# DAQ.net
KiCad netlist of a schematic drawn in EAGLE
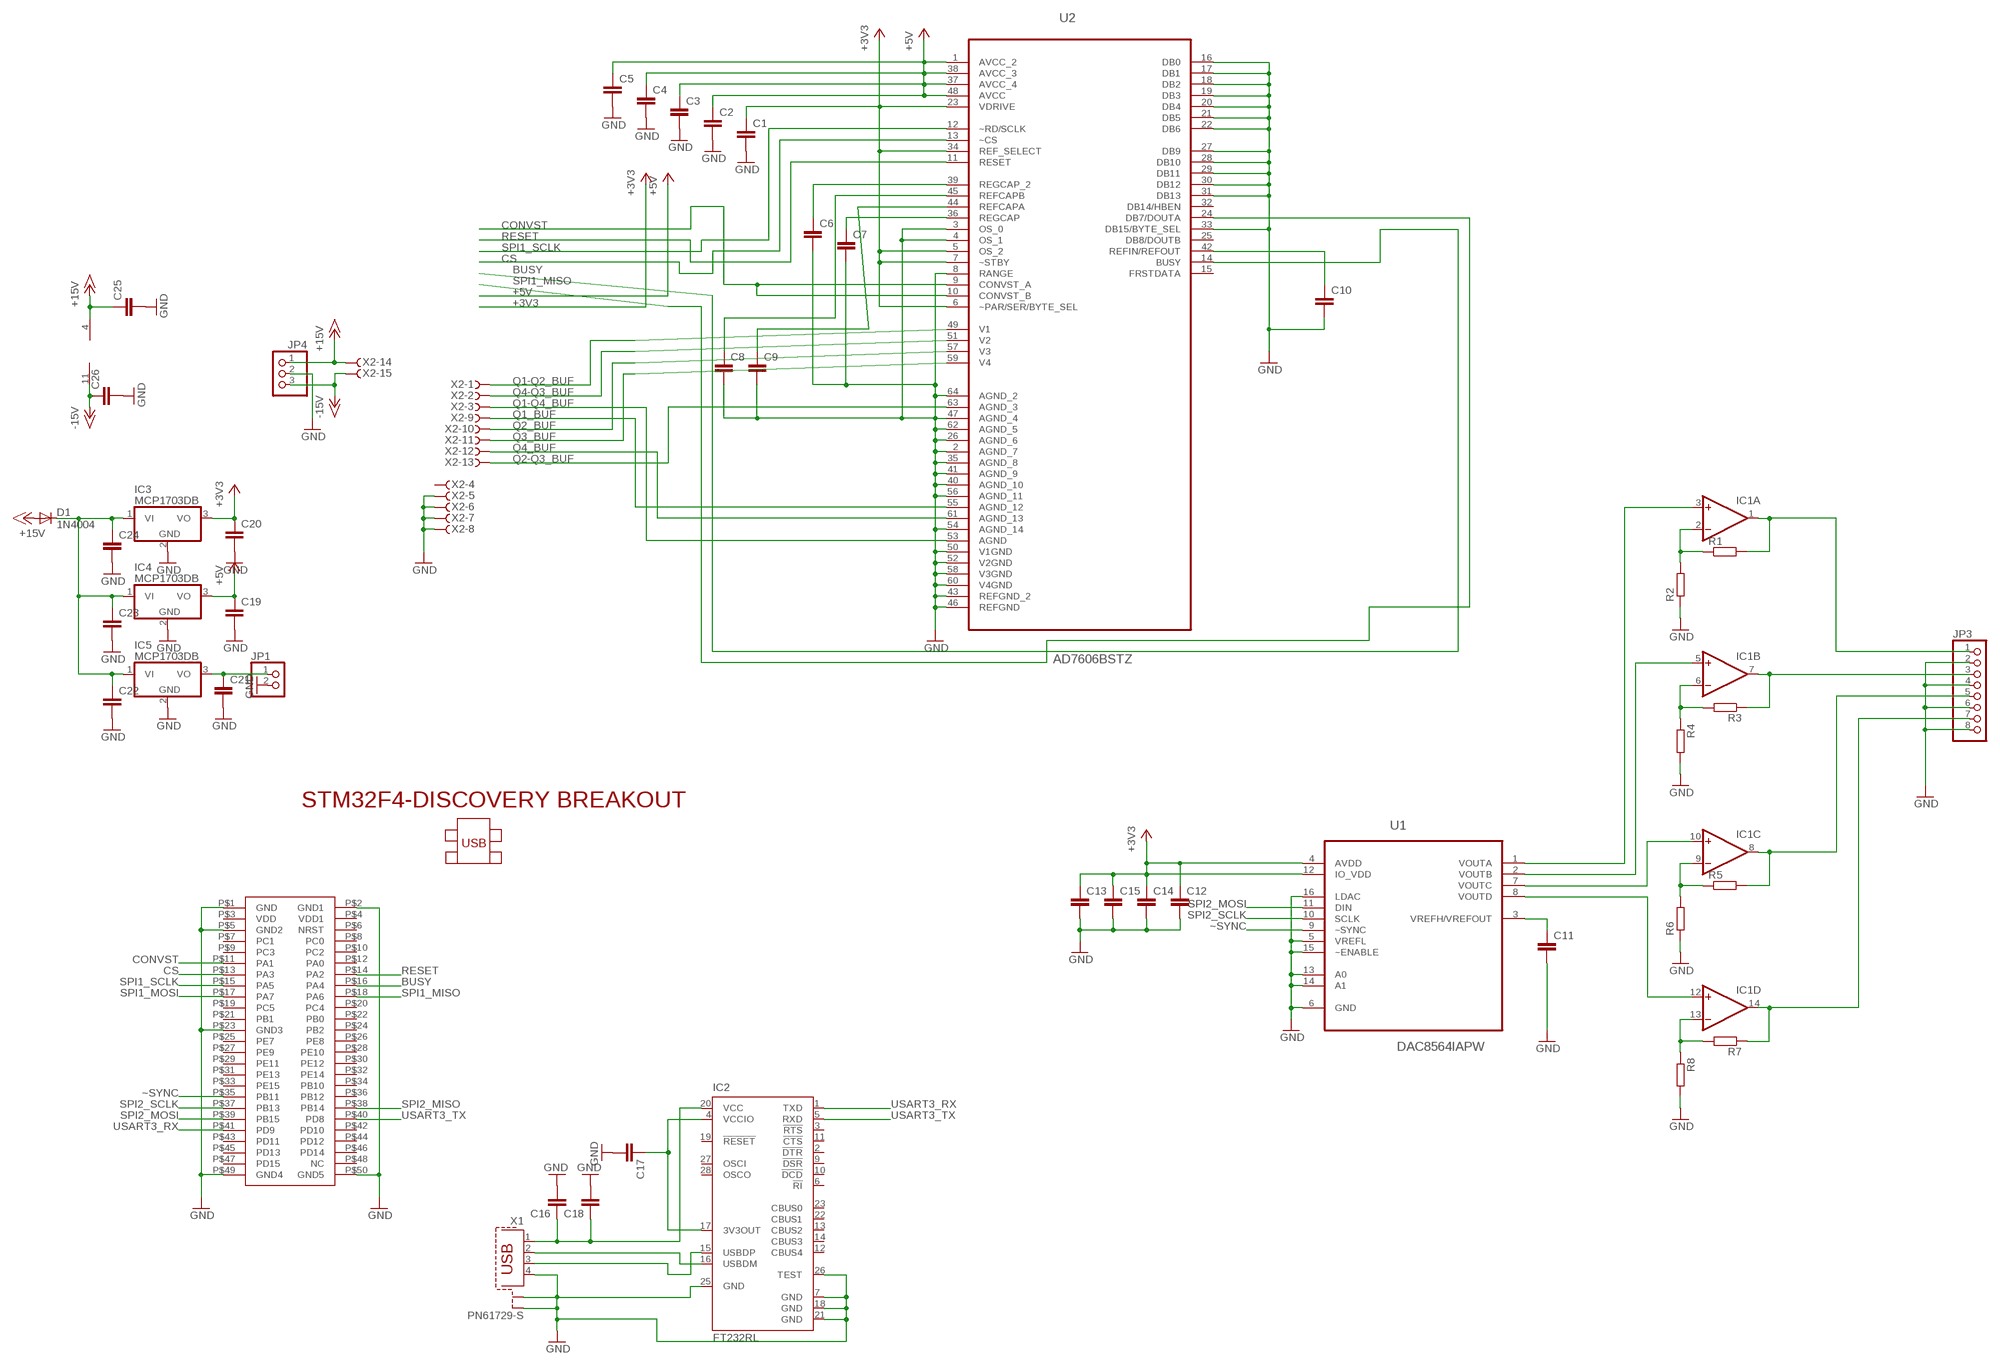
[diagram p0: schematic, sheet 1]

(export (version "E")
  (design (tool "Eeschema 10.0.6"))
  (components
    (comp (ref "C1")
      (value "C-EUC0805")
      (footprint "eagle-import:C0805")
      (libsource (lib "eagle-import") (part "C-EUC0805"))
    )
    (comp (ref "C2")
      (value "C-EUC0805")
      (footprint "eagle-import:C0805")
      (libsource (lib "eagle-import") (part "C-EUC0805"))
    )
    (comp (ref "C3")
      (value "C-EUC0805")
      (footprint "eagle-import:C0805")
      (libsource (lib "eagle-import") (part "C-EUC0805"))
    )
    (comp (ref "C4")
      (value "C-EUC0805")
      (footprint "eagle-import:C0805")
      (libsource (lib "eagle-import") (part "C-EUC0805"))
    )
    (comp (ref "C5")
      (value "C-EUC0805")
      (footprint "eagle-import:C0805")
      (libsource (lib "eagle-import") (part "C-EUC0805"))
    )
    (comp (ref "C6")
      (value "C-EUC0805")
      (footprint "eagle-import:C0805")
      (libsource (lib "eagle-import") (part "C-EUC0805"))
    )
    (comp (ref "C7")
      (value "C-EUC0805")
      (footprint "eagle-import:C0805")
      (libsource (lib "eagle-import") (part "C-EUC0805"))
    )
    (comp (ref "C8")
      (value "C-EUC0805K")
      (footprint "eagle-import:C0805K")
      (libsource (lib "eagle-import") (part "C-EUC0805K"))
    )
    (comp (ref "C9")
      (value "C-EUC0805K")
      (footprint "eagle-import:C0805K")
      (libsource (lib "eagle-import") (part "C-EUC0805K"))
    )
    (comp (ref "C10")
      (value "C-EUC0805K")
      (footprint "eagle-import:C0805K")
      (libsource (lib "eagle-import") (part "C-EUC0805K"))
    )
    (comp (ref "C11")
      (value "C-EUC0805")
      (footprint "eagle-import:C0805")
      (libsource (lib "eagle-import") (part "C-EUC0805"))
    )
    (comp (ref "C12")
      (value "C-EUC0805")
      (footprint "eagle-import:C0805")
      (libsource (lib "eagle-import") (part "C-EUC0805"))
    )
    (comp (ref "C13")
      (value "C-EUC0805")
      (footprint "eagle-import:C0805")
      (libsource (lib "eagle-import") (part "C-EUC0805"))
    )
    (comp (ref "C14")
      (value "C-EUC0805")
      (footprint "eagle-import:C0805")
      (libsource (lib "eagle-import") (part "C-EUC0805"))
    )
    (comp (ref "C15")
      (value "C-EUC0805")
      (footprint "eagle-import:C0805")
      (libsource (lib "eagle-import") (part "C-EUC0805"))
    )
    (comp (ref "C16")
      (value "C-EUC0805")
      (footprint "eagle-import:C0805")
      (libsource (lib "eagle-import") (part "C-EUC0805"))
    )
    (comp (ref "C17")
      (value "C-EUC0805")
      (footprint "eagle-import:C0805")
      (libsource (lib "eagle-import") (part "C-EUC0805"))
    )
    (comp (ref "C18")
      (value "C-EUC0805")
      (footprint "eagle-import:C0805")
      (libsource (lib "eagle-import") (part "C-EUC0805"))
    )
    (comp (ref "C19")
      (value "C-EUC0805K")
      (footprint "eagle-import:C0805K")
      (libsource (lib "eagle-import") (part "C-EUC0805K"))
    )
    (comp (ref "C20")
      (value "C-EUC0805K")
      (footprint "eagle-import:C0805K")
      (libsource (lib "eagle-import") (part "C-EUC0805K"))
    )
    (comp (ref "C21")
      (value "C-EUC0805K")
      (footprint "eagle-import:C0805K")
      (libsource (lib "eagle-import") (part "C-EUC0805K"))
    )
    (comp (ref "C22")
      (value "C-EUC0805K")
      (footprint "eagle-import:C0805K")
      (libsource (lib "eagle-import") (part "C-EUC0805K"))
    )
    (comp (ref "C23")
      (value "C-EUC0805K")
      (footprint "eagle-import:C0805K")
      (libsource (lib "eagle-import") (part "C-EUC0805K"))
    )
    (comp (ref "C24")
      (value "C-EUC0805K")
      (footprint "eagle-import:C0805K")
      (libsource (lib "eagle-import") (part "C-EUC0805K"))
    )
    (comp (ref "C25")
      (value "C-EUC0805K")
      (footprint "eagle-import:C0805K")
      (libsource (lib "eagle-import") (part "C-EUC0805K"))
    )
    (comp (ref "C26")
      (value "C-EUC0805K")
      (footprint "eagle-import:C0805K")
      (libsource (lib "eagle-import") (part "C-EUC0805K"))
    )
    (comp (ref "D1")
      (value "1N4004")
      (footprint "eagle-import:DO41-10")
      (libsource (lib "eagle-import") (part "1N4004"))
    )
    (comp (ref "IC1")
      (value "4AMP_P4+11D")
      (footprint "eagle-import:SO14")
      (libsource (lib "eagle-import") (part "4AMP_P4+11D"))
    )
    (comp (ref "IC2")
      (value "FT232RL")
      (footprint "eagle-import:SSOP28")
      (libsource (lib "eagle-import") (part "FT232RL"))
    )
    (comp (ref "IC3")
      (value "MCP1703DB")
      (footprint "eagle-import:SOT223")
      (libsource (lib "eagle-import") (part "MCP1703DB"))
    )
    (comp (ref "IC4")
      (value "MCP1703DB")
      (footprint "eagle-import:SOT223")
      (libsource (lib "eagle-import") (part "MCP1703DB"))
    )
    (comp (ref "IC5")
      (value "MCP1703DB")
      (footprint "eagle-import:SOT223")
      (libsource (lib "eagle-import") (part "MCP1703DB"))
    )
    (comp (ref "JP1")
      (value "PINHD-1X2")
      (footprint "eagle-import:1X02")
      (libsource (lib "eagle-import") (part "PINHD-1X2"))
    )
    (comp (ref "JP3")
      (value "PINHD-1X8")
      (footprint "eagle-import:1X08")
      (libsource (lib "eagle-import") (part "PINHD-1X8"))
    )
    (comp (ref "JP4")
      (value "PINHD-1X3")
      (footprint "eagle-import:1X03")
      (libsource (lib "eagle-import") (part "PINHD-1X3"))
    )
    (comp (ref "R1")
      (value "R-EU_M0805")
      (footprint "eagle-import:M0805")
      (libsource (lib "eagle-import") (part "R-EU_M0805"))
    )
    (comp (ref "R2")
      (value "R-EU_M0805")
      (footprint "eagle-import:M0805")
      (libsource (lib "eagle-import") (part "R-EU_M0805"))
    )
    (comp (ref "R3")
      (value "R-EU_M0805")
      (footprint "eagle-import:M0805")
      (libsource (lib "eagle-import") (part "R-EU_M0805"))
    )
    (comp (ref "R4")
      (value "R-EU_M0805")
      (footprint "eagle-import:M0805")
      (libsource (lib "eagle-import") (part "R-EU_M0805"))
    )
    (comp (ref "R5")
      (value "R-EU_M0805")
      (footprint "eagle-import:M0805")
      (libsource (lib "eagle-import") (part "R-EU_M0805"))
    )
    (comp (ref "R6")
      (value "R-EU_M0805")
      (footprint "eagle-import:M0805")
      (libsource (lib "eagle-import") (part "R-EU_M0805"))
    )
    (comp (ref "R7")
      (value "R-EU_M0805")
      (footprint "eagle-import:M0805")
      (libsource (lib "eagle-import") (part "R-EU_M0805"))
    )
    (comp (ref "R8")
      (value "R-EU_M0805")
      (footprint "eagle-import:M0805")
      (libsource (lib "eagle-import") (part "R-EU_M0805"))
    )
    (comp (ref "U$1")
      (value "STM32F4-DISCOVERY")
      (footprint "eagle-import:STM32F4-DISCOVERY")
      (libsource (lib "eagle-import") (part "STM32F4-DISCOVERY"))
    )
    (comp (ref "U1")
      (value "DAC8564IAPW")
      (footprint "eagle-import:SOP65P640X120-16N")
      (libsource (lib "eagle-import") (part "DAC8564IAPW"))
    )
    (comp (ref "U2")
      (value "AD7606BSTZ")
      (footprint "eagle-import:QFP50P1200X1200X160-64N")
      (libsource (lib "eagle-import") (part "AD7606BSTZ"))
    )
    (comp (ref "X1")
      (value "PN61729-S")
      (footprint "eagle-import:PN61729-S")
      (libsource (lib "eagle-import") (part "PN61729-S"))
    )
    (comp (ref "X2")
      (value "F15HDHS")
      (footprint "eagle-import:HDF15H")
      (libsource (lib "eagle-import") (part "F15?SHDH"))
    )
  )
  (nets
    (net (code "1") (name "+3V3") (class "Default")
      (node (ref "C1") (pin "1") (pinfunction "1_1") (pintype "passive"))
      (node (ref "C12") (pin "1") (pinfunction "1_1") (pintype "passive"))
      (node (ref "C13") (pin "1") (pinfunction "1_1") (pintype "passive"))
      (node (ref "C14") (pin "1") (pinfunction "1_1") (pintype "passive"))
      (node (ref "C15") (pin "1") (pinfunction "1_1") (pintype "passive"))
      (node (ref "C20") (pin "1") (pinfunction "1_1") (pintype "passive"))
      (node (ref "IC3") (pin "3") (pinfunction "VO_3") (pintype "passive"))
      (node (ref "U1") (pin "12") (pinfunction "IO_VDD_12") (pintype "power_in"))
      (node (ref "U1") (pin "4") (pinfunction "AVDD_4") (pintype "power_in"))
      (node (ref "U2") (pin "23") (pinfunction "VDRIVE_23") (pintype "power_in"))
      (node (ref "U2") (pin "34") (pinfunction "REF_SELECT_34") (pintype "input"))
      (node (ref "U2") (pin "5") (pinfunction "OS_2_5") (pintype "input"))
      (node (ref "U2") (pin "6") (pinfunction "~{PAR/SER/BYTE_SEL}_6") (pintype "input"))
      (node (ref "U2") (pin "7") (pinfunction "~{STBY}_7") (pintype "input"))
    )
    (net (code "2") (name "+5V") (class "Default")
      (node (ref "C19") (pin "1") (pinfunction "1_1") (pintype "passive"))
      (node (ref "C2") (pin "1") (pinfunction "1_1") (pintype "passive"))
      (node (ref "C3") (pin "1") (pinfunction "1_1") (pintype "passive"))
      (node (ref "C4") (pin "1") (pinfunction "1_1") (pintype "passive"))
      (node (ref "C5") (pin "1") (pinfunction "1_1") (pintype "passive"))
      (node (ref "IC4") (pin "3") (pinfunction "VO_3") (pintype "passive"))
      (node (ref "U2") (pin "1") (pinfunction "AVCC_2_1") (pintype "power_in"))
      (node (ref "U2") (pin "37") (pinfunction "AVCC_4_37") (pintype "power_in"))
      (node (ref "U2") (pin "38") (pinfunction "AVCC_3_38") (pintype "power_in"))
      (node (ref "U2") (pin "48") (pinfunction "AVCC_48") (pintype "power_in"))
    )
    (net (code "3") (name "+15V") (class "Default")
      (node (ref "C25") (pin "1") (pinfunction "1_1") (pintype "passive"))
      (node (ref "D1") (pin "A") (pinfunction "A_A") (pintype "passive"))
      (node (ref "IC1") (pin "4") (pinfunction "V+_4") (pintype "power_in"))
      (node (ref "JP4") (pin "1") (pinfunction "1_1") (pintype "passive"))
      (node (ref "X2") (pin "14") (pinfunction "F_14") (pintype "passive"))
    )
    (net (code "4") (name "-15V") (class "Default")
      (node (ref "C26") (pin "1") (pinfunction "1_1") (pintype "passive"))
      (node (ref "IC1") (pin "11") (pinfunction "V-_11") (pintype "power_in"))
      (node (ref "JP4") (pin "3") (pinfunction "3_3") (pintype "passive"))
      (node (ref "X2") (pin "15") (pinfunction "F_15") (pintype "passive"))
    )
    (net (code "5") (name "/BUSY") (class "Default")
      (node (ref "U$1") (pin "P$16") (pinfunction "PA4_P$16") (pintype "bidirectional"))
      (node (ref "U2") (pin "14") (pinfunction "BUSY_14") (pintype "output"))
    )
    (net (code "6") (name "/CONVST") (class "Default")
      (node (ref "U$1") (pin "P$11") (pinfunction "PA1_P$11") (pintype "bidirectional"))
      (node (ref "U2") (pin "10") (pinfunction "CONVST_B_10") (pintype "input"))
      (node (ref "U2") (pin "9") (pinfunction "CONVST_A_9") (pintype "input"))
    )
    (net (code "7") (name "/CS") (class "Default")
      (node (ref "U$1") (pin "P$13") (pinfunction "PA3_P$13") (pintype "bidirectional"))
      (node (ref "U2") (pin "13") (pinfunction "~{CS}_13") (pintype "input"))
    )
    (net (code "8") (name "/Q1-Q2_BUF") (class "Default")
      (node (ref "U2") (pin "49") (pinfunction "V1_49") (pintype "input"))
      (node (ref "X2") (pin "1") (pinfunction "F_1") (pintype "passive"))
    )
    (net (code "9") (name "/Q1-Q4_BUF") (class "Default")
      (node (ref "U2") (pin "53") (pinfunction "AGND_53") (pintype "passive"))
      (node (ref "X2") (pin "3") (pinfunction "F_3") (pintype "passive"))
    )
    (net (code "10") (name "/Q1_BUF") (class "Default")
      (node (ref "U2") (pin "55") (pinfunction "AGND_12_55") (pintype "passive"))
      (node (ref "X2") (pin "9") (pinfunction "F_9") (pintype "passive"))
    )
    (net (code "11") (name "/Q2-Q3_BUF") (class "Default")
      (node (ref "U2") (pin "63") (pinfunction "AGND_3_63") (pintype "passive"))
      (node (ref "X2") (pin "13") (pinfunction "F_13") (pintype "passive"))
    )
    (net (code "12") (name "/Q2_BUF") (class "Default")
      (node (ref "U2") (pin "57") (pinfunction "V3_57") (pintype "input"))
      (node (ref "X2") (pin "10") (pinfunction "F_10") (pintype "passive"))
    )
    (net (code "13") (name "/Q3_BUF") (class "Default")
      (node (ref "U2") (pin "59") (pinfunction "V4_59") (pintype "input"))
      (node (ref "X2") (pin "11") (pinfunction "F_11") (pintype "passive"))
    )
    (net (code "14") (name "/Q4-Q3_BUF") (class "Default")
      (node (ref "U2") (pin "51") (pinfunction "V2_51") (pintype "input"))
      (node (ref "X2") (pin "2") (pinfunction "F_2") (pintype "passive"))
    )
    (net (code "15") (name "/Q4_BUF") (class "Default")
      (node (ref "U2") (pin "61") (pinfunction "AGND_13_61") (pintype "passive"))
      (node (ref "X2") (pin "12") (pinfunction "F_12") (pintype "passive"))
    )
    (net (code "16") (name "/RESET") (class "Default")
      (node (ref "U$1") (pin "P$14") (pinfunction "PA2_P$14") (pintype "bidirectional"))
      (node (ref "U2") (pin "11") (pinfunction "RESET_11") (pintype "input"))
    )
    (net (code "17") (name "/SPI1_MISO") (class "Default")
      (node (ref "U$1") (pin "P$18") (pinfunction "PA6_P$18") (pintype "bidirectional"))
      (node (ref "U2") (pin "24") (pinfunction "DB7/DOUTA_24") (pintype "output"))
    )
    (net (code "18") (name "/SPI1_MOSI") (class "Default")
      (node (ref "U$1") (pin "P$17") (pinfunction "PA7_P$17") (pintype "bidirectional"))
    )
    (net (code "19") (name "/SPI1_SCLK") (class "Default")
      (node (ref "U$1") (pin "P$15") (pinfunction "PA5_P$15") (pintype "bidirectional"))
      (node (ref "U2") (pin "12") (pinfunction "~{RD/SCLK}_12") (pintype "input"))
    )
    (net (code "20") (name "/SPI2_MISO") (class "Default")
      (node (ref "U$1") (pin "P$38") (pinfunction "PB14_P$38") (pintype "bidirectional"))
    )
    (net (code "21") (name "/SPI2_MOSI") (class "Default")
      (node (ref "U$1") (pin "P$39") (pinfunction "PB15_P$39") (pintype "bidirectional"))
      (node (ref "U1") (pin "11") (pinfunction "DIN_11") (pintype "input"))
    )
    (net (code "22") (name "/SPI2_SCLK") (class "Default")
      (node (ref "U$1") (pin "P$37") (pinfunction "PB13_P$37") (pintype "bidirectional"))
      (node (ref "U1") (pin "10") (pinfunction "SCLK_10") (pintype "input"))
    )
    (net (code "23") (name "/USART3_RX") (class "Default")
      (node (ref "IC2") (pin "1") (pinfunction "TXD_1") (pintype "output"))
      (node (ref "U$1") (pin "P$41") (pinfunction "PD9_P$41") (pintype "bidirectional"))
    )
    (net (code "24") (name "/USART3_TX") (class "Default")
      (node (ref "IC2") (pin "5") (pinfunction "RXD_5") (pintype "input"))
      (node (ref "U$1") (pin "P$40") (pinfunction "PD8_P$40") (pintype "bidirectional"))
    )
    (net (code "25") (name "/~{SYNC}") (class "Default")
      (node (ref "U$1") (pin "P$35") (pinfunction "PB11_P$35") (pintype "bidirectional"))
      (node (ref "U1") (pin "9") (pinfunction "~{SYNC}_9") (pintype "input"))
    )
    (net (code "26") (name "GND") (class "Default")
      (node (ref "C1") (pin "2") (pinfunction "2_2") (pintype "passive"))
      (node (ref "C10") (pin "2") (pinfunction "2_2") (pintype "passive"))
      (node (ref "C11") (pin "2") (pinfunction "2_2") (pintype "passive"))
      (node (ref "C12") (pin "2") (pinfunction "2_2") (pintype "passive"))
      (node (ref "C13") (pin "2") (pinfunction "2_2") (pintype "passive"))
      (node (ref "C14") (pin "2") (pinfunction "2_2") (pintype "passive"))
      (node (ref "C15") (pin "2") (pinfunction "2_2") (pintype "passive"))
      (node (ref "C16") (pin "2") (pinfunction "2_2") (pintype "passive"))
      (node (ref "C17") (pin "2") (pinfunction "2_2") (pintype "passive"))
      (node (ref "C18") (pin "2") (pinfunction "2_2") (pintype "passive"))
      (node (ref "C19") (pin "2") (pinfunction "2_2") (pintype "passive"))
      (node (ref "C2") (pin "2") (pinfunction "2_2") (pintype "passive"))
      (node (ref "C20") (pin "2") (pinfunction "2_2") (pintype "passive"))
      (node (ref "C21") (pin "2") (pinfunction "2_2") (pintype "passive"))
      (node (ref "C22") (pin "2") (pinfunction "2_2") (pintype "passive"))
      (node (ref "C23") (pin "2") (pinfunction "2_2") (pintype "passive"))
      (node (ref "C24") (pin "2") (pinfunction "2_2") (pintype "passive"))
      (node (ref "C25") (pin "2") (pinfunction "2_2") (pintype "passive"))
      (node (ref "C26") (pin "2") (pinfunction "2_2") (pintype "passive"))
      (node (ref "C3") (pin "2") (pinfunction "2_2") (pintype "passive"))
      (node (ref "C4") (pin "2") (pinfunction "2_2") (pintype "passive"))
      (node (ref "C5") (pin "2") (pinfunction "2_2") (pintype "passive"))
      (node (ref "C6") (pin "2") (pinfunction "2_2") (pintype "passive"))
      (node (ref "C7") (pin "2") (pinfunction "2_2") (pintype "passive"))
      (node (ref "C8") (pin "2") (pinfunction "2_2") (pintype "passive"))
      (node (ref "C9") (pin "2") (pinfunction "2_2") (pintype "passive"))
      (node (ref "IC2") (pin "18") (pinfunction "GND_18") (pintype "power_in"))
      (node (ref "IC2") (pin "21") (pinfunction "GND_21") (pintype "power_in"))
      (node (ref "IC2") (pin "25") (pinfunction "GND_25") (pintype "power_in"))
      (node (ref "IC2") (pin "26") (pinfunction "TEST_26") (pintype "input"))
      (node (ref "IC2") (pin "7") (pinfunction "GND_7") (pintype "power_in"))
      (node (ref "IC3") (pin "2") (pinfunction "GND_2") (pintype "passive"))
      (node (ref "IC4") (pin "2") (pinfunction "GND_2") (pintype "passive"))
      (node (ref "IC5") (pin "2") (pinfunction "GND_2") (pintype "passive"))
      (node (ref "JP1") (pin "2") (pinfunction "2_2") (pintype "passive"))
      (node (ref "JP3") (pin "2") (pinfunction "2_2") (pintype "passive"))
      (node (ref "JP3") (pin "4") (pinfunction "4_4") (pintype "passive"))
      (node (ref "JP3") (pin "6") (pinfunction "6_6") (pintype "passive"))
      (node (ref "JP3") (pin "8") (pinfunction "8_8") (pintype "passive"))
      (node (ref "JP4") (pin "2") (pinfunction "2_2") (pintype "passive"))
      (node (ref "R2") (pin "1") (pinfunction "1_1") (pintype "passive"))
      (node (ref "R4") (pin "2") (pinfunction "2_2") (pintype "passive"))
      (node (ref "R6") (pin "1") (pinfunction "1_1") (pintype "passive"))
      (node (ref "R8") (pin "2") (pinfunction "2_2") (pintype "passive"))
      (node (ref "U$1") (pin "P$1") (pinfunction "GND_P$1") (pintype "bidirectional"))
      (node (ref "U$1") (pin "P$2") (pinfunction "GND1_P$2") (pintype "bidirectional"))
      (node (ref "U$1") (pin "P$23") (pinfunction "GND3_P$23") (pintype "bidirectional"))
      (node (ref "U$1") (pin "P$49") (pinfunction "GND4_P$49") (pintype "bidirectional"))
      (node (ref "U$1") (pin "P$5") (pinfunction "GND2_P$5") (pintype "bidirectional"))
      (node (ref "U$1") (pin "P$50") (pinfunction "GND5_P$50") (pintype "bidirectional"))
      (node (ref "U1") (pin "13") (pinfunction "A0_13") (pintype "input"))
      (node (ref "U1") (pin "14") (pinfunction "A1_14") (pintype "input"))
      (node (ref "U1") (pin "15") (pinfunction "~{ENABLE}_15") (pintype "input"))
      (node (ref "U1") (pin "16") (pinfunction "LDAC_16") (pintype "input"))
      (node (ref "U1") (pin "5") (pinfunction "VREFL_5") (pintype "input"))
      (node (ref "U1") (pin "6") (pinfunction "GND_6") (pintype "passive"))
      (node (ref "U2") (pin "16") (pinfunction "DB0_16") (pintype "output"))
      (node (ref "U2") (pin "17") (pinfunction "DB1_17") (pintype "output"))
      (node (ref "U2") (pin "18") (pinfunction "DB2_18") (pintype "output"))
      (node (ref "U2") (pin "19") (pinfunction "DB3_19") (pintype "output"))
      (node (ref "U2") (pin "2") (pinfunction "AGND_7_2") (pintype "passive"))
      (node (ref "U2") (pin "20") (pinfunction "DB4_20") (pintype "output"))
      (node (ref "U2") (pin "21") (pinfunction "DB5_21") (pintype "output"))
      (node (ref "U2") (pin "22") (pinfunction "DB6_22") (pintype "output"))
      (node (ref "U2") (pin "26") (pinfunction "AGND_6_26") (pintype "passive"))
      (node (ref "U2") (pin "27") (pinfunction "DB9_27") (pintype "output"))
      (node (ref "U2") (pin "28") (pinfunction "DB10_28") (pintype "output"))
      (node (ref "U2") (pin "29") (pinfunction "DB11_29") (pintype "output"))
      (node (ref "U2") (pin "3") (pinfunction "OS_0_3") (pintype "input"))
      (node (ref "U2") (pin "30") (pinfunction "DB12_30") (pintype "output"))
      (node (ref "U2") (pin "31") (pinfunction "DB13_31") (pintype "output"))
      (node (ref "U2") (pin "33") (pinfunction "DB15/BYTE_SEL_33") (pintype "output"))
      (node (ref "U2") (pin "35") (pinfunction "AGND_8_35") (pintype "passive"))
      (node (ref "U2") (pin "4") (pinfunction "OS_1_4") (pintype "input"))
      (node (ref "U2") (pin "40") (pinfunction "AGND_10_40") (pintype "passive"))
      (node (ref "U2") (pin "41") (pinfunction "AGND_9_41") (pintype "passive"))
      (node (ref "U2") (pin "43") (pinfunction "REFGND_2_43") (pintype "passive"))
      (node (ref "U2") (pin "46") (pinfunction "REFGND_46") (pintype "passive"))
      (node (ref "U2") (pin "47") (pinfunction "AGND_4_47") (pintype "passive"))
      (node (ref "U2") (pin "50") (pinfunction "V1GND_50") (pintype "passive"))
      (node (ref "U2") (pin "52") (pinfunction "V2GND_52") (pintype "passive"))
      (node (ref "U2") (pin "54") (pinfunction "AGND_14_54") (pintype "passive"))
      (node (ref "U2") (pin "56") (pinfunction "AGND_11_56") (pintype "passive"))
      (node (ref "U2") (pin "58") (pinfunction "V3GND_58") (pintype "passive"))
      (node (ref "U2") (pin "60") (pinfunction "V4GND_60") (pintype "passive"))
      (node (ref "U2") (pin "62") (pinfunction "AGND_5_62") (pintype "passive"))
      (node (ref "U2") (pin "64") (pinfunction "AGND_2_64") (pintype "passive"))
      (node (ref "U2") (pin "8") (pinfunction "RANGE_8") (pintype "input"))
      (node (ref "X1") (pin "4") (pinfunction "4_4") (pintype "passive"))
      (node (ref "X1") (pin "S1") (pinfunction "S1_S1") (pintype "passive"))
      (node (ref "X1") (pin "S2") (pinfunction "S2_S2") (pintype "passive"))
      (node (ref "X2") (pin "5") (pinfunction "F_5") (pintype "passive"))
      (node (ref "X2") (pin "6") (pinfunction "F_6") (pintype "passive"))
      (node (ref "X2") (pin "7") (pinfunction "F_7") (pintype "passive"))
      (node (ref "X2") (pin "8") (pinfunction "F_8") (pintype "passive"))
    )
    (net (code "27") (name "Net-(IC1A-+IN)") (class "Default")
      (node (ref "IC1") (pin "3") (pinfunction "+IN_3") (pintype "input"))
      (node (ref "U1") (pin "1") (pinfunction "VOUTA_1") (pintype "output"))
    )
    (net (code "28") (name "Net-(IC1A--IN)") (class "Default")
      (node (ref "IC1") (pin "2") (pinfunction "-IN_2") (pintype "input"))
      (node (ref "R1") (pin "1") (pinfunction "1_1") (pintype "passive"))
      (node (ref "R2") (pin "2") (pinfunction "2_2") (pintype "passive"))
    )
    (net (code "29") (name "Net-(IC1A-OUT)") (class "Default")
      (node (ref "IC1") (pin "1") (pinfunction "OUT_1") (pintype "output"))
      (node (ref "JP3") (pin "1") (pinfunction "1_1") (pintype "passive"))
      (node (ref "R1") (pin "2") (pinfunction "2_2") (pintype "passive"))
    )
    (net (code "30") (name "Net-(IC1B-+IN)") (class "Default")
      (node (ref "IC1") (pin "5") (pinfunction "+IN_5") (pintype "input"))
      (node (ref "U1") (pin "2") (pinfunction "VOUTB_2") (pintype "output"))
    )
    (net (code "31") (name "Net-(IC1B--IN)") (class "Default")
      (node (ref "IC1") (pin "6") (pinfunction "-IN_6") (pintype "input"))
      (node (ref "R3") (pin "2") (pinfunction "2_2") (pintype "passive"))
      (node (ref "R4") (pin "1") (pinfunction "1_1") (pintype "passive"))
    )
    (net (code "32") (name "Net-(IC1B-OUT)") (class "Default")
      (node (ref "IC1") (pin "7") (pinfunction "OUT_7") (pintype "output"))
      (node (ref "JP3") (pin "3") (pinfunction "3_3") (pintype "passive"))
      (node (ref "R3") (pin "1") (pinfunction "1_1") (pintype "passive"))
    )
    (net (code "33") (name "Net-(IC1C-+IN)") (class "Default")
      (node (ref "IC1") (pin "10") (pinfunction "+IN_10") (pintype "input"))
      (node (ref "U1") (pin "7") (pinfunction "VOUTC_7") (pintype "output"))
    )
    (net (code "34") (name "Net-(IC1C--IN)") (class "Default")
      (node (ref "IC1") (pin "9") (pinfunction "-IN_9") (pintype "input"))
      (node (ref "R5") (pin "1") (pinfunction "1_1") (pintype "passive"))
      (node (ref "R6") (pin "2") (pinfunction "2_2") (pintype "passive"))
    )
    (net (code "35") (name "Net-(IC1C-OUT)") (class "Default")
      (node (ref "IC1") (pin "8") (pinfunction "OUT_8") (pintype "output"))
      (node (ref "JP3") (pin "5") (pinfunction "5_5") (pintype "passive"))
      (node (ref "R5") (pin "2") (pinfunction "2_2") (pintype "passive"))
    )
    (net (code "36") (name "Net-(IC1D-+IN)") (class "Default")
      (node (ref "IC1") (pin "12") (pinfunction "+IN_12") (pintype "input"))
      (node (ref "U1") (pin "8") (pinfunction "VOUTD_8") (pintype "output"))
    )
    (net (code "37") (name "Net-(IC1D--IN)") (class "Default")
      (node (ref "IC1") (pin "13") (pinfunction "-IN_13") (pintype "input"))
      (node (ref "R7") (pin "2") (pinfunction "2_2") (pintype "passive"))
      (node (ref "R8") (pin "1") (pinfunction "1_1") (pintype "passive"))
    )
    (net (code "38") (name "Net-(IC1D-OUT)") (class "Default")
      (node (ref "IC1") (pin "14") (pinfunction "OUT_14") (pintype "output"))
      (node (ref "JP3") (pin "7") (pinfunction "7_7") (pintype "passive"))
      (node (ref "R7") (pin "1") (pinfunction "1_1") (pintype "passive"))
    )
    (net (code "39") (name "Net-(IC2-3V3OUT)") (class "Default")
      (node (ref "C17") (pin "1") (pinfunction "1_1") (pintype "passive"))
      (node (ref "IC2") (pin "17") (pinfunction "3V3OUT_17") (pintype "output"))
      (node (ref "IC2") (pin "4") (pinfunction "VCCIO_4") (pintype "power_in"))
    )
    (net (code "40") (name "Net-(IC2-USBDM)") (class "Default")
      (node (ref "IC2") (pin "16") (pinfunction "USBDM_16") (pintype "bidirectional"))
      (node (ref "X1") (pin "2") (pinfunction "2_2") (pintype "passive"))
    )
    (net (code "41") (name "Net-(IC2-USBDP)") (class "Default")
      (node (ref "IC2") (pin "15") (pinfunction "USBDP_15") (pintype "bidirectional"))
      (node (ref "X1") (pin "3") (pinfunction "3_3") (pintype "passive"))
    )
    (net (code "42") (name "Net-(IC2-VCC)") (class "Default")
      (node (ref "C16") (pin "1") (pinfunction "1_1") (pintype "passive"))
      (node (ref "C18") (pin "1") (pinfunction "1_1") (pintype "passive"))
      (node (ref "IC2") (pin "20") (pinfunction "VCC_20") (pintype "power_in"))
      (node (ref "X1") (pin "1") (pinfunction "1_1") (pintype "passive"))
    )
    (net (code "43") (name "Net-(IC3-VI)") (class "Default")
      (node (ref "C22") (pin "1") (pinfunction "1_1") (pintype "passive"))
      (node (ref "C23") (pin "1") (pinfunction "1_1") (pintype "passive"))
      (node (ref "C24") (pin "1") (pinfunction "1_1") (pintype "passive"))
      (node (ref "D1") (pin "C") (pinfunction "C_C") (pintype "passive"))
      (node (ref "IC3") (pin "1") (pinfunction "VI_1") (pintype "input"))
      (node (ref "IC4") (pin "1") (pinfunction "VI_1") (pintype "input"))
      (node (ref "IC5") (pin "1") (pinfunction "VI_1") (pintype "input"))
    )
    (net (code "44") (name "Net-(IC5-VO)") (class "Default")
      (node (ref "C21") (pin "1") (pinfunction "1_1") (pintype "passive"))
      (node (ref "IC5") (pin "3") (pinfunction "VO_3") (pintype "passive"))
      (node (ref "JP1") (pin "1") (pinfunction "1_1") (pintype "passive"))
    )
    (net (code "45") (name "Net-(U1-VREFH{slash}VREFOUT)") (class "Default")
      (node (ref "C11") (pin "1") (pinfunction "1_1") (pintype "passive"))
      (node (ref "U1") (pin "3") (pinfunction "VREFH/VREFOUT_3") (pintype "bidirectional"))
    )
    (net (code "46") (name "Net-(U2-REFCAPA)") (class "Default")
      (node (ref "C9") (pin "1") (pinfunction "1_1") (pintype "passive"))
      (node (ref "U2") (pin "44") (pinfunction "REFCAPA_44") (pintype "passive"))
    )
    (net (code "47") (name "Net-(U2-REFCAPB)") (class "Default")
      (node (ref "C8") (pin "1") (pinfunction "1_1") (pintype "passive"))
      (node (ref "U2") (pin "45") (pinfunction "REFCAPB_45") (pintype "passive"))
    )
    (net (code "48") (name "Net-(U2-REFIN{slash}REFOUT)") (class "Default")
      (node (ref "C10") (pin "1") (pinfunction "1_1") (pintype "passive"))
      (node (ref "U2") (pin "42") (pinfunction "REFIN/REFOUT_42") (pintype "output"))
    )
    (net (code "49") (name "Net-(U2-REGCAP)") (class "Default")
      (node (ref "C7") (pin "1") (pinfunction "1_1") (pintype "passive"))
      (node (ref "U2") (pin "36") (pinfunction "REGCAP_36") (pintype "passive"))
    )
    (net (code "50") (name "Net-(U2-REGCAP_2)") (class "Default")
      (node (ref "C6") (pin "1") (pinfunction "1_1") (pintype "passive"))
      (node (ref "U2") (pin "39") (pinfunction "REGCAP_2_39") (pintype "passive"))
    )
    (net (code "51") (name "unconnected-(IC2-CBUS0-Pad23)") (class "Default")
      (node (ref "IC2") (pin "23") (pinfunction "CBUS0_23") (pintype "bidirectional"))
    )
    (net (code "52") (name "unconnected-(IC2-CBUS1-Pad22)") (class "Default")
      (node (ref "IC2") (pin "22") (pinfunction "CBUS1_22") (pintype "bidirectional"))
    )
    (net (code "53") (name "unconnected-(IC2-CBUS2-Pad13)") (class "Default")
      (node (ref "IC2") (pin "13") (pinfunction "CBUS2_13") (pintype "bidirectional"))
    )
    (net (code "54") (name "unconnected-(IC2-CBUS3-Pad14)") (class "Default")
      (node (ref "IC2") (pin "14") (pinfunction "CBUS3_14") (pintype "bidirectional"))
    )
    (net (code "55") (name "unconnected-(IC2-CBUS4-Pad12)") (class "Default")
      (node (ref "IC2") (pin "12") (pinfunction "CBUS4_12") (pintype "bidirectional"))
    )
    (net (code "56") (name "unconnected-(IC2-OSCI-Pad27)") (class "Default")
      (node (ref "IC2") (pin "27") (pinfunction "OSCI_27") (pintype "input"))
    )
    (net (code "57") (name "unconnected-(IC2-OSCO-Pad28)") (class "Default")
      (node (ref "IC2") (pin "28") (pinfunction "OSCO_28") (pintype "output"))
    )
    (net (code "58") (name "unconnected-(IC2-~{CTS}-Pad11)") (class "Default")
      (node (ref "IC2") (pin "11") (pinfunction "~{CTS}_11") (pintype "input"))
    )
    (net (code "59") (name "unconnected-(IC2-~{DCD}-Pad10)") (class "Default")
      (node (ref "IC2") (pin "10") (pinfunction "~{DCD}_10") (pintype "input"))
    )
    (net (code "60") (name "unconnected-(IC2-~{DSR}-Pad9)") (class "Default")
      (node (ref "IC2") (pin "9") (pinfunction "~{DSR}_9") (pintype "input"))
    )
    (net (code "61") (name "unconnected-(IC2-~{DTR}-Pad2)") (class "Default")
      (node (ref "IC2") (pin "2") (pinfunction "~{DTR}_2") (pintype "output"))
    )
    (net (code "62") (name "unconnected-(IC2-~{RESET}-Pad19)") (class "Default")
      (node (ref "IC2") (pin "19") (pinfunction "~{RESET}_19") (pintype "input"))
    )
    (net (code "63") (name "unconnected-(IC2-~{RI}-Pad6)") (class "Default")
      (node (ref "IC2") (pin "6") (pinfunction "~{RI}_6") (pintype "input"))
    )
    (net (code "64") (name "unconnected-(IC2-~{RTS}-Pad3)") (class "Default")
      (node (ref "IC2") (pin "3") (pinfunction "~{RTS}_3") (pintype "output"))
    )
    (net (code "65") (name "unconnected-(U$1-NC-PadP$48)") (class "Default")
      (node (ref "U$1") (pin "P$48") (pinfunction "NC_P$48") (pintype "bidirectional"))
    )
    (net (code "66") (name "unconnected-(U$1-NRST-PadP$6)") (class "Default")
      (node (ref "U$1") (pin "P$6") (pinfunction "NRST_P$6") (pintype "bidirectional"))
    )
    (net (code "67") (name "unconnected-(U$1-PA0-PadP$12)") (class "Default")
      (node (ref "U$1") (pin "P$12") (pinfunction "PA0_P$12") (pintype "bidirectional"))
    )
    (net (code "68") (name "unconnected-(U$1-PB0-PadP$22)") (class "Default")
      (node (ref "U$1") (pin "P$22") (pinfunction "PB0_P$22") (pintype "bidirectional"))
    )
    (net (code "69") (name "unconnected-(U$1-PB1-PadP$21)") (class "Default")
      (node (ref "U$1") (pin "P$21") (pinfunction "PB1_P$21") (pintype "bidirectional"))
    )
    (net (code "70") (name "unconnected-(U$1-PB2-PadP$24)") (class "Default")
      (node (ref "U$1") (pin "P$24") (pinfunction "PB2_P$24") (pintype "bidirectional"))
    )
    (net (code "71") (name "unconnected-(U$1-PB10-PadP$34)") (class "Default")
      (node (ref "U$1") (pin "P$34") (pinfunction "PB10_P$34") (pintype "bidirectional"))
    )
    (net (code "72") (name "unconnected-(U$1-PB12-PadP$36)") (class "Default")
      (node (ref "U$1") (pin "P$36") (pinfunction "PB12_P$36") (pintype "bidirectional"))
    )
    (net (code "73") (name "unconnected-(U$1-PC0-PadP$8)") (class "Default")
      (node (ref "U$1") (pin "P$8") (pinfunction "PC0_P$8") (pintype "bidirectional"))
    )
    (net (code "74") (name "unconnected-(U$1-PC1-PadP$7)") (class "Default")
      (node (ref "U$1") (pin "P$7") (pinfunction "PC1_P$7") (pintype "bidirectional"))
    )
    (net (code "75") (name "unconnected-(U$1-PC2-PadP$10)") (class "Default")
      (node (ref "U$1") (pin "P$10") (pinfunction "PC2_P$10") (pintype "bidirectional"))
    )
    (net (code "76") (name "unconnected-(U$1-PC3-PadP$9)") (class "Default")
      (node (ref "U$1") (pin "P$9") (pinfunction "PC3_P$9") (pintype "bidirectional"))
    )
    (net (code "77") (name "unconnected-(U$1-PC4-PadP$20)") (class "Default")
      (node (ref "U$1") (pin "P$20") (pinfunction "PC4_P$20") (pintype "bidirectional"))
    )
    (net (code "78") (name "unconnected-(U$1-PC5-PadP$19)") (class "Default")
      (node (ref "U$1") (pin "P$19") (pinfunction "PC5_P$19") (pintype "bidirectional"))
    )
    (net (code "79") (name "unconnected-(U$1-PD10-PadP$42)") (class "Default")
      (node (ref "U$1") (pin "P$42") (pinfunction "PD10_P$42") (pintype "bidirectional"))
    )
    (net (code "80") (name "unconnected-(U$1-PD11-PadP$43)") (class "Default")
      (node (ref "U$1") (pin "P$43") (pinfunction "PD11_P$43") (pintype "bidirectional"))
    )
    (net (code "81") (name "unconnected-(U$1-PD12-PadP$44)") (class "Default")
      (node (ref "U$1") (pin "P$44") (pinfunction "PD12_P$44") (pintype "bidirectional"))
    )
    (net (code "82") (name "unconnected-(U$1-PD13-PadP$45)") (class "Default")
      (node (ref "U$1") (pin "P$45") (pinfunction "PD13_P$45") (pintype "bidirectional"))
    )
    (net (code "83") (name "unconnected-(U$1-PD14-PadP$46)") (class "Default")
      (node (ref "U$1") (pin "P$46") (pinfunction "PD14_P$46") (pintype "bidirectional"))
    )
    (net (code "84") (name "unconnected-(U$1-PD15-PadP$47)") (class "Default")
      (node (ref "U$1") (pin "P$47") (pinfunction "PD15_P$47") (pintype "bidirectional"))
    )
    (net (code "85") (name "unconnected-(U$1-PE7-PadP$25)") (class "Default")
      (node (ref "U$1") (pin "P$25") (pinfunction "PE7_P$25") (pintype "bidirectional"))
    )
    (net (code "86") (name "unconnected-(U$1-PE8-PadP$26)") (class "Default")
      (node (ref "U$1") (pin "P$26") (pinfunction "PE8_P$26") (pintype "bidirectional"))
    )
    (net (code "87") (name "unconnected-(U$1-PE9-PadP$27)") (class "Default")
      (node (ref "U$1") (pin "P$27") (pinfunction "PE9_P$27") (pintype "bidirectional"))
    )
    (net (code "88") (name "unconnected-(U$1-PE10-PadP$28)") (class "Default")
      (node (ref "U$1") (pin "P$28") (pinfunction "PE10_P$28") (pintype "bidirectional"))
    )
    (net (code "89") (name "unconnected-(U$1-PE11-PadP$29)") (class "Default")
      (node (ref "U$1") (pin "P$29") (pinfunction "PE11_P$29") (pintype "bidirectional"))
    )
    (net (code "90") (name "unconnected-(U$1-PE12-PadP$30)") (class "Default")
      (node (ref "U$1") (pin "P$30") (pinfunction "PE12_P$30") (pintype "bidirectional"))
    )
    (net (code "91") (name "unconnected-(U$1-PE13-PadP$31)") (class "Default")
      (node (ref "U$1") (pin "P$31") (pinfunction "PE13_P$31") (pintype "bidirectional"))
    )
    (net (code "92") (name "unconnected-(U$1-PE14-PadP$32)") (class "Default")
      (node (ref "U$1") (pin "P$32") (pinfunction "PE14_P$32") (pintype "bidirectional"))
    )
    (net (code "93") (name "unconnected-(U$1-PE15-PadP$33)") (class "Default")
      (node (ref "U$1") (pin "P$33") (pinfunction "PE15_P$33") (pintype "bidirectional"))
    )
    (net (code "94") (name "unconnected-(U$1-VDD-PadP$3)") (class "Default")
      (node (ref "U$1") (pin "P$3") (pinfunction "VDD_P$3") (pintype "bidirectional"))
    )
    (net (code "95") (name "unconnected-(U$1-VDD1-PadP$4)") (class "Default")
      (node (ref "U$1") (pin "P$4") (pinfunction "VDD1_P$4") (pintype "bidirectional"))
    )
    (net (code "96") (name "unconnected-(U2-DB8{slash}DOUTB-Pad25)") (class "Default")
      (node (ref "U2") (pin "25") (pinfunction "DB8/DOUTB_25") (pintype "output"))
    )
    (net (code "97") (name "unconnected-(U2-DB14{slash}HBEN-Pad32)") (class "Default")
      (node (ref "U2") (pin "32") (pinfunction "DB14/HBEN_32") (pintype "output"))
    )
    (net (code "98") (name "unconnected-(U2-FRSTDATA-Pad15)") (class "Default")
      (node (ref "U2") (pin "15") (pinfunction "FRSTDATA_15") (pintype "output"))
    )
    (net (code "99") (name "unconnected-(X2J-F-Pad4)") (class "Default")
      (node (ref "X2") (pin "4") (pinfunction "F_4") (pintype "passive"))
    )
  )
)
